# PCA9540BD_small_breakout.net
KiCad netlist of a schematic drawn in EAGLE
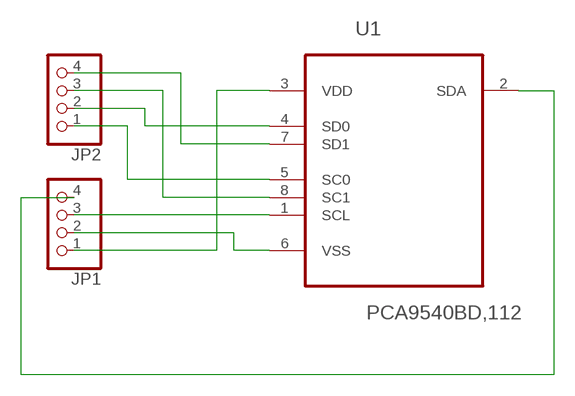
[diagram p0: schematic, sheet 1]

(export (version "E")
  (design (tool "Eeschema 10.0.6"))
  (components
    (comp (ref "JP1")
      (value "PINHD-1X4")
      (footprint "eagle-import:1X04")
      (libsource (lib "eagle-import") (part "PINHD-1X4"))
    )
    (comp (ref "JP2")
      (value "PINHD-1X4")
      (footprint "eagle-import:1X04")
      (libsource (lib "eagle-import") (part "PINHD-1X4"))
    )
    (comp (ref "U1")
      (value "PCA9540BD,112")
      (footprint "eagle-import:SOIC127P600X175-8N")
      (libsource (lib "eagle-import") (part "PCA9540BD,112"))
    )
  )
  (nets
    (net (code "1") (name "Net-(U1-SC0)") (class "Default")
      (node (ref "JP2") (pin "1") (pinfunction "1_1") (pintype "passive"))
      (node (ref "U1") (pin "5") (pinfunction "SC0_5") (pintype "input"))
    )
    (net (code "2") (name "Net-(U1-SC1)") (class "Default")
      (node (ref "JP2") (pin "3") (pinfunction "3_3") (pintype "passive"))
      (node (ref "U1") (pin "8") (pinfunction "SC1_8") (pintype "input"))
    )
    (net (code "3") (name "Net-(U1-SCL)") (class "Default")
      (node (ref "JP1") (pin "3") (pinfunction "3_3") (pintype "passive"))
      (node (ref "U1") (pin "1") (pinfunction "SCL_1") (pintype "input"))
    )
    (net (code "4") (name "Net-(U1-SD0)") (class "Default")
      (node (ref "JP2") (pin "2") (pinfunction "2_2") (pintype "passive"))
      (node (ref "U1") (pin "4") (pinfunction "SD0_4") (pintype "bidirectional"))
    )
    (net (code "5") (name "Net-(U1-SD1)") (class "Default")
      (node (ref "JP2") (pin "4") (pinfunction "4_4") (pintype "passive"))
      (node (ref "U1") (pin "7") (pinfunction "SD1_7") (pintype "bidirectional"))
    )
    (net (code "6") (name "Net-(U1-SDA)") (class "Default")
      (node (ref "JP1") (pin "4") (pinfunction "4_4") (pintype "passive"))
      (node (ref "U1") (pin "2") (pinfunction "SDA_2") (pintype "bidirectional"))
    )
    (net (code "7") (name "Net-(U1-VDD)") (class "Default")
      (node (ref "JP1") (pin "1") (pinfunction "1_1") (pintype "passive"))
      (node (ref "U1") (pin "3") (pinfunction "VDD_3") (pintype "power_in"))
    )
    (net (code "8") (name "Net-(U1-VSS)") (class "Default")
      (node (ref "JP1") (pin "2") (pinfunction "2_2") (pintype "passive"))
      (node (ref "U1") (pin "6") (pinfunction "VSS_6") (pintype "power_in"))
    )
  )
)
